# 2_power_supply.net
KiCad netlist of a schematic drawn in Altium Designer
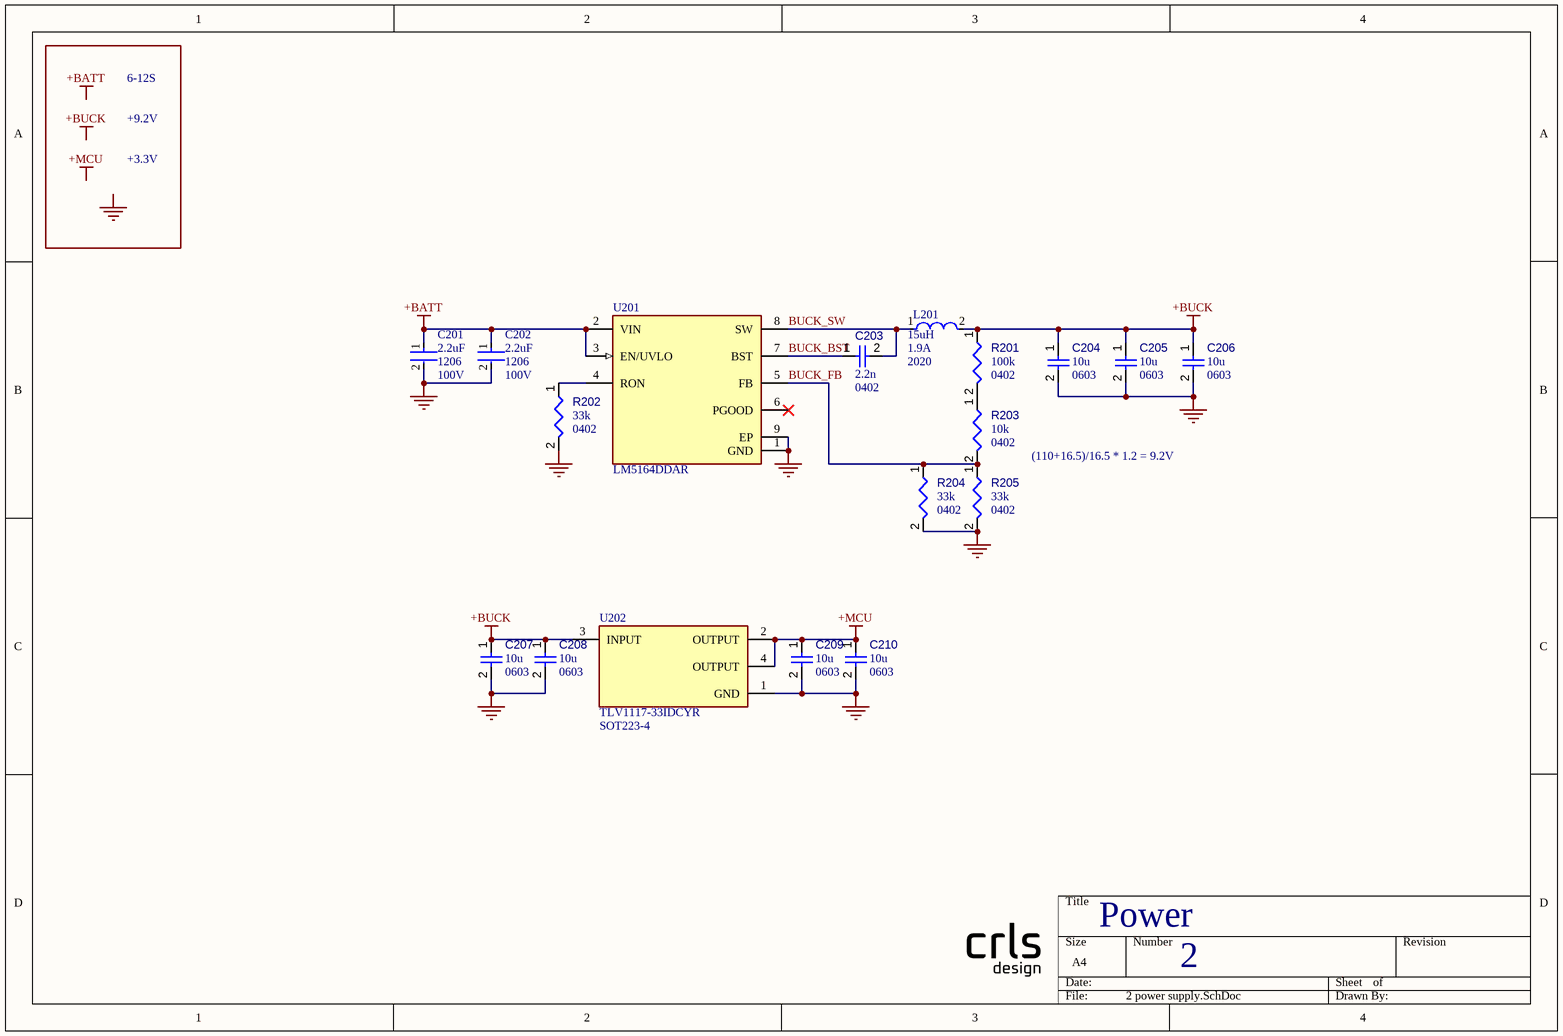
[diagram p0: 2 power supply.SchDoc]

(export (version "E")
  (design (tool "Eeschema 10.0.6"))
  (components
    (comp (ref "C201")
      (value "CC1206KKX7R0BB225")
      (footprint "FP-CC1206-0_3-1_9-MFG")
      (description "CAP CER 2.2UF 100V X7R 1206")
      (fields
        (field (name "VOLTAGE RATING") "100V")
        (field (name "CASE/PACKAGE") "1206")
        (field (name "CAPACITANCE") "2.2uF")
        (field (name "TOLERANCE") "10%")
      )
      (libsource (lib "Altium Content Vault") (part "b4654b650e69147ec39a6b967a45e02"))
    )
    (comp (ref "C202")
      (value "CC1206KKX7R0BB225")
      (footprint "FP-CC1206-0_3-1_9-MFG")
      (description "CAP CER 2.2UF 100V X7R 1206")
      (fields
        (field (name "VOLTAGE RATING") "100V")
        (field (name "CASE/PACKAGE") "1206")
        (field (name "CAPACITANCE") "2.2uF")
        (field (name "TOLERANCE") "10%")
      )
      (libsource (lib "Altium Content Vault") (part "b4654b650e69147ec39a6b967a45e02"))
    )
    (comp (ref "C203")
      (value "2.2n")
      (footprint "CAPC0402(1005)60_L")
      (description "Capacitor")
      (fields
        (field (name "CASE/PACKAGE") "0402")
        (field (name "TOLERANCE") "10%")
        (field (name "Comment") "Capacitors,ceramic,0402,10%,2.2n,50V")
      )
      (libsource (lib "UBC Uncrewed Aircraft Systems") (part "CAP-NP-2"))
    )
    (comp (ref "C204")
      (value "10u")
      (footprint "CAPC0603(1608)100_L")
      (description "Capacitor")
      (fields
        (field (name "CASE/PACKAGE") "0603")
        (field (name "TOLERANCE") "20%")
        (field (name "Comment") "Capacitors,ceramic,0603,20%,10u,25V")
      )
      (libsource (lib "UBC Uncrewed Aircraft Systems") (part "CAP-NP-2"))
    )
    (comp (ref "C205")
      (value "10u")
      (footprint "CAPC0603(1608)100_L")
      (description "Capacitor")
      (fields
        (field (name "CASE/PACKAGE") "0603")
        (field (name "TOLERANCE") "20%")
        (field (name "Comment") "Capacitors,ceramic,0603,20%,10u,25V")
      )
      (libsource (lib "UBC Uncrewed Aircraft Systems") (part "CAP-NP-2"))
    )
    (comp (ref "C206")
      (value "10u")
      (footprint "CAPC0603(1608)100_L")
      (description "Capacitor")
      (fields
        (field (name "CASE/PACKAGE") "0603")
        (field (name "TOLERANCE") "20%")
        (field (name "Comment") "Capacitors,ceramic,0603,20%,10u,25V")
      )
      (libsource (lib "UBC Uncrewed Aircraft Systems") (part "CAP-NP-2"))
    )
    (comp (ref "C207")
      (value "10u")
      (footprint "CAPC0603(1608)100_L")
      (description "Capacitor")
      (fields
        (field (name "CASE/PACKAGE") "0603")
        (field (name "TOLERANCE") "20%")
        (field (name "Comment") "Capacitors,ceramic,0603,20%,10u,25V")
      )
      (libsource (lib "UBC Uncrewed Aircraft Systems") (part "CAP-NP-2"))
    )
    (comp (ref "C208")
      (value "10u")
      (footprint "CAPC0603(1608)100_L")
      (description "Capacitor")
      (fields
        (field (name "CASE/PACKAGE") "0603")
        (field (name "TOLERANCE") "20%")
        (field (name "Comment") "Capacitors,ceramic,0603,20%,10u,25V")
      )
      (libsource (lib "UBC Uncrewed Aircraft Systems") (part "CAP-NP-2"))
    )
    (comp (ref "C209")
      (value "10u")
      (footprint "CAPC0603(1608)100_L")
      (description "Capacitor")
      (fields
        (field (name "CASE/PACKAGE") "0603")
        (field (name "TOLERANCE") "20%")
        (field (name "Comment") "Capacitors,ceramic,0603,20%,10u,25V")
      )
      (libsource (lib "UBC Uncrewed Aircraft Systems") (part "CAP-NP-2"))
    )
    (comp (ref "C210")
      (value "10u")
      (footprint "CAPC0603(1608)100_L")
      (description "Capacitor")
      (fields
        (field (name "CASE/PACKAGE") "0603")
        (field (name "TOLERANCE") "20%")
        (field (name "Comment") "Capacitors,ceramic,0603,20%,10u,25V")
      )
      (libsource (lib "UBC Uncrewed Aircraft Systems") (part "CAP-NP-2"))
    )
    (comp (ref "L201")
      (value "IHLP2020CZER150M01")
      (footprint "FP-IHLP-2020CZ-FP_1_905x2-MFG")
      (description "Fixed Inductors Commercial High Saturation Series 15uH 1.9A 265mΩ 20%")
      (fields
        (field (name "CASE/PACKAGE") "2020")
        (field (name "CURRENT RATING") "1.9A")
        (field (name "INDUCTANCE") "15uH")
        (field (name "TOLERANCE") "20%")
      )
      (libsource (lib "Altium Content Vault") (part "725321dda6339637d4d059423bc1c3c"))
    )
    (comp (ref "R201")
      (value "100k")
      (footprint "RESC0402(1005)_L")
      (description "Resistor")
      (fields
        (field (name "CASE/PACKAGE") "0402")
        (field (name "TOLERANCE") "1%")
        (field (name "Comment") "Resistors,0402,1%,100k")
      )
      (libsource (lib "UBC Uncrewed Aircraft Systems") (part "RES-2"))
    )
    (comp (ref "R202")
      (value "33k")
      (footprint "RESC0402(1005)_L")
      (description "Resistor")
      (fields
        (field (name "CASE/PACKAGE") "0402")
        (field (name "TOLERANCE") "1%")
        (field (name "Comment") "Resistors,0402,1%,33k")
      )
      (libsource (lib "UBC Uncrewed Aircraft Systems") (part "RES-2"))
    )
    (comp (ref "R203")
      (value "10k")
      (footprint "RESC0402(1005)_L")
      (description "Resistor")
      (fields
        (field (name "CASE/PACKAGE") "0402")
        (field (name "TOLERANCE") "1%")
        (field (name "Comment") "Resistors,0402,1%,10k")
      )
      (libsource (lib "UBC Uncrewed Aircraft Systems") (part "RES-2"))
    )
    (comp (ref "R204")
      (value "33k")
      (footprint "RESC0402(1005)_L")
      (description "Resistor")
      (fields
        (field (name "CASE/PACKAGE") "0402")
        (field (name "TOLERANCE") "1%")
        (field (name "Comment") "Resistors,0402,1%,33k")
      )
      (libsource (lib "UBC Uncrewed Aircraft Systems") (part "RES-2"))
    )
    (comp (ref "R205")
      (value "33k")
      (footprint "RESC0402(1005)_L")
      (description "Resistor")
      (fields
        (field (name "CASE/PACKAGE") "0402")
        (field (name "TOLERANCE") "1%")
        (field (name "Comment") "Resistors,0402,1%,33k")
      )
      (libsource (lib "UBC Uncrewed Aircraft Systems") (part "RES-2"))
    )
    (comp (ref "U201")
      (value "LM5164DDAR")
      (footprint "FP-DDA0008E-IPC_C")
      (description "POWER MANAGEMENT")
      (fields
        (field (name "MANUFACTURER") "Texas Instruments")
        (field (name "OCTOPART") "https://octopart.com/lm5164ddar-texas+instruments-96785744")
      )
      (libsource (lib "Altium Content Vault") (part "ad4762e8767f3654d2dc1ed5c3dee12"))
    )
    (comp (ref "U202")
      (value "TLV1117-33IDCYR")
      (footprint "FP-DCY0004A-MFG")
      (description "IC REG LIN 3.3V 800MA SOT223-4")
      (fields
        (field (name "MANUFACTURER") "Texas Instruments")
        (field (name "OCTOPART") "https://octopart.com/tlv1117-33idcyr-texas+instruments-669250")
        (field (name "PACKAGE") "SOT223-4")
      )
      (libsource (lib "Altium Content Vault") (part "d420fb9686013fb832e66295cdf4acf"))
    )
  )
  (nets
    (net (code "1") (name "+BATT") (class "Default")
      (node (ref "C201") (pin "1") (pinfunction "1_1") (pintype "passive"))
      (node (ref "C202") (pin "1") (pinfunction "1_1") (pintype "passive"))
      (node (ref "U201") (pin "2") (pinfunction "VIN_2") (pintype "power_in"))
      (node (ref "U201") (pin "3") (pinfunction "EN/UVLO_3") (pintype "input"))
    )
    (net (code "2") (name "+BUCK") (class "Default")
      (node (ref "C204") (pin "1") (pinfunction "1_1") (pintype "passive"))
      (node (ref "C205") (pin "1") (pinfunction "1_1") (pintype "passive"))
      (node (ref "C206") (pin "1") (pinfunction "1_1") (pintype "passive"))
      (node (ref "C207") (pin "1") (pinfunction "1_1") (pintype "passive"))
      (node (ref "C208") (pin "1") (pinfunction "1_1") (pintype "passive"))
      (node (ref "L201") (pin "2") (pinfunction "2_2") (pintype "passive"))
      (node (ref "R201") (pin "1") (pinfunction "1_1") (pintype "passive"))
      (node (ref "U202") (pin "3") (pinfunction "INPUT_3") (pintype "power_in"))
    )
    (net (code "3") (name "+MCU") (class "Default")
      (node (ref "C209") (pin "1") (pinfunction "1_1") (pintype "passive"))
      (node (ref "C210") (pin "1") (pinfunction "1_1") (pintype "passive"))
      (node (ref "U202") (pin "2") (pinfunction "OUTPUT_2") (pintype "power_in"))
      (node (ref "U202") (pin "4") (pinfunction "OUTPUT_4") (pintype "power_in"))
    )
    (net (code "4") (name "/BUCK_BST") (class "Default")
      (node (ref "C203") (pin "1") (pinfunction "1_1") (pintype "passive"))
      (node (ref "U201") (pin "7") (pinfunction "BST_7") (pintype "passive"))
    )
    (net (code "5") (name "/BUCK_FB") (class "Default")
      (node (ref "R203") (pin "2") (pinfunction "2_2") (pintype "passive"))
      (node (ref "R204") (pin "1") (pinfunction "1_1") (pintype "passive"))
      (node (ref "R205") (pin "1") (pinfunction "1_1") (pintype "passive"))
      (node (ref "U201") (pin "5") (pinfunction "FB_5") (pintype "passive"))
    )
    (net (code "6") (name "/BUCK_SW") (class "Default")
      (node (ref "C203") (pin "2") (pinfunction "2_2") (pintype "passive"))
      (node (ref "L201") (pin "1") (pinfunction "1_1") (pintype "passive"))
      (node (ref "U201") (pin "8") (pinfunction "SW_8") (pintype "passive"))
    )
    (net (code "7") (name "GND") (class "Default")
      (node (ref "C201") (pin "2") (pinfunction "2_2") (pintype "passive"))
      (node (ref "C202") (pin "2") (pinfunction "2_2") (pintype "passive"))
      (node (ref "C204") (pin "2") (pinfunction "2_2") (pintype "passive"))
      (node (ref "C205") (pin "2") (pinfunction "2_2") (pintype "passive"))
      (node (ref "C206") (pin "2") (pinfunction "2_2") (pintype "passive"))
      (node (ref "C207") (pin "2") (pinfunction "2_2") (pintype "passive"))
      (node (ref "C208") (pin "2") (pinfunction "2_2") (pintype "passive"))
      (node (ref "C209") (pin "2") (pinfunction "2_2") (pintype "passive"))
      (node (ref "C210") (pin "2") (pinfunction "2_2") (pintype "passive"))
      (node (ref "R202") (pin "2") (pinfunction "2_2") (pintype "passive"))
      (node (ref "R204") (pin "2") (pinfunction "2_2") (pintype "passive"))
      (node (ref "R205") (pin "2") (pinfunction "2_2") (pintype "passive"))
      (node (ref "U201") (pin "1") (pinfunction "GND_1") (pintype "power_in"))
      (node (ref "U201") (pin "9") (pinfunction "EP_9") (pintype "passive"))
      (node (ref "U202") (pin "1") (pinfunction "GND_1") (pintype "power_in"))
    )
    (net (code "8") (name "Net-(R201-Pad2)") (class "Default")
      (node (ref "R201") (pin "2") (pinfunction "2_2") (pintype "passive"))
      (node (ref "R203") (pin "1") (pinfunction "1_1") (pintype "passive"))
    )
    (net (code "9") (name "Net-(U201-RON)") (class "Default")
      (node (ref "R202") (pin "1") (pinfunction "1_1") (pintype "passive"))
      (node (ref "U201") (pin "4") (pinfunction "RON_4") (pintype "passive"))
    )
    (net (code "10") (name "unconnected-(U201-PGOOD-Pad6)") (class "Default")
      (node (ref "U201") (pin "6") (pinfunction "PGOOD_6") (pintype "open_collector+no_connect"))
    )
  )
)
